# amp-33dbm.net
KiCad netlist of a schematic drawn in Altium Designer
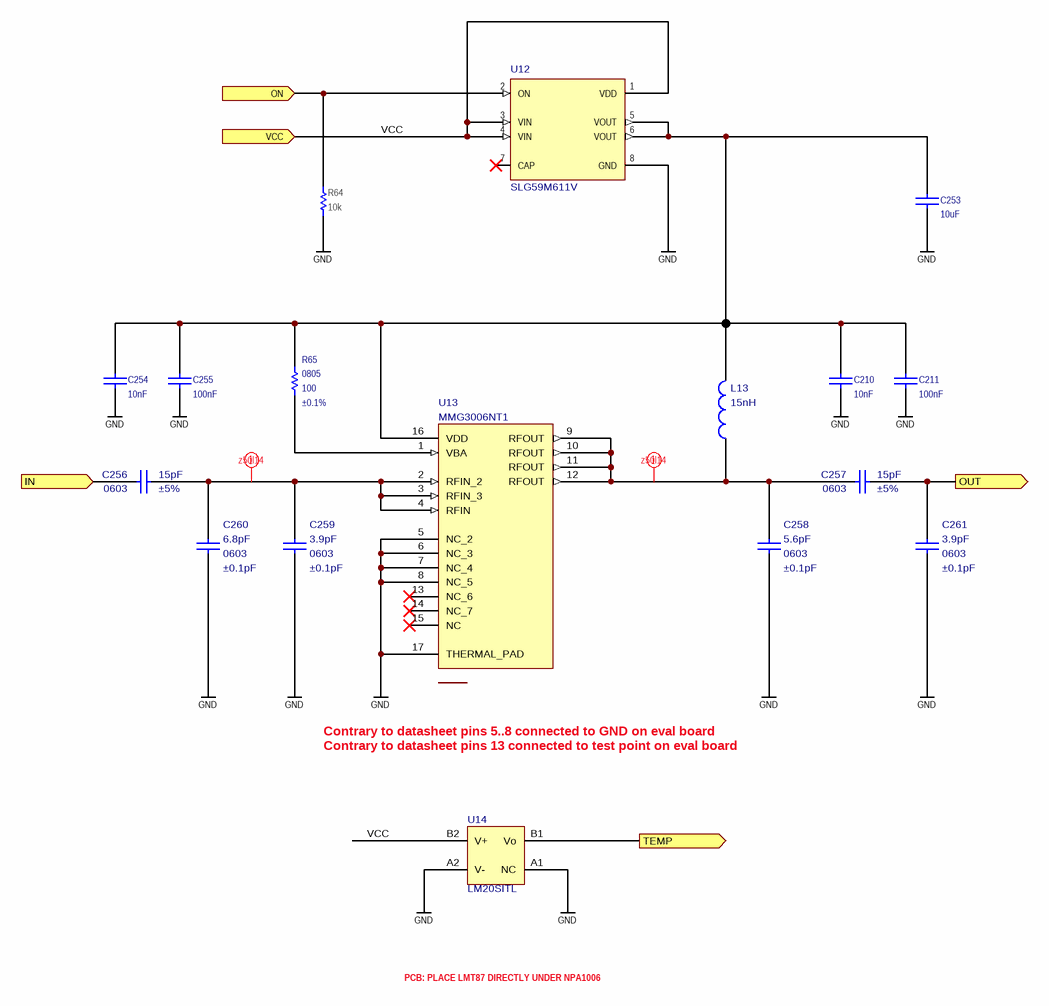
[diagram p0: amp-33dbm.SchDoc]

(export (version "E")
  (design (tool "Eeschema 10.0.6"))
  (components
    (comp (ref "C210")
      (value "10nF")
      (footprint "CAPC100X50X55L25N")
      (description "Ceramic Capacitor 10nF ±10% 50V X7R 0402")
      (fields (field (name "VOLTAGE") "50V") (field (name "MANUFACTURER") "Murata"))
      (libsource (lib "Graviton") (part "CAP 0402"))
    )
    (comp (ref "C211")
      (value "100nF")
      (footprint "CAPC100X50X55L25N")
      (description "Ceramic Capacitor 100nF ±10% 16V X7R 0402")
      (fields (field (name "VOLTAGE") "16V") (field (name "MANUFACTURER") "Murata"))
      (libsource (lib "Graviton") (part "CAP 0402"))
    )
    (comp (ref "C253")
      (value "10uF")
      (footprint "CAPC160X80X90L20N")
      (description "Ceramic Capacitor 10uF ±20% 25V X5R 0603")
      (fields (field (name "MANUFACTURER") "Murata") (field (name "VOLTAGE") "25V"))
      (libsource (lib "generic") (part "CAP 0603"))
    )
    (comp (ref "C254")
      (value "10nF")
      (footprint "CAPC100X50X55L25N")
      (description "Ceramic Capacitor 10nF ±10% 50V X7R 0402")
      (fields (field (name "VOLTAGE") "50V") (field (name "MANUFACTURER") "Murata"))
      (libsource (lib "Graviton") (part "CAP 0402"))
    )
    (comp (ref "C255")
      (value "100nF")
      (footprint "CAPC100X50X55L25N")
      (description "Ceramic Capacitor 100nF ±10% 16V X7R 0402")
      (fields (field (name "VOLTAGE") "16V") (field (name "MANUFACTURER") "Murata"))
      (libsource (lib "Graviton") (part "CAP 0402"))
    )
    (comp (ref "C256")
      (value "15pF")
      (footprint "CAPC160X80X90L20N")
      (description "Ceramic Capacitor 15pF ±5% NP0 0603")
      (fields
        (field (name "MANUFACTURER") "Murata")
        (field (name "TOLERANCE") "±5%")
        (field (name "VOLTAGE") "50V")
        (field (name "PACKAGE") "0603")
      )
      (libsource (lib "generic") (part "CAP"))
    )
    (comp (ref "C257")
      (value "15pF")
      (footprint "CAPC160X80X90L20N")
      (description "Ceramic Capacitor 15pF ±5% NP0 0603")
      (fields
        (field (name "MANUFACTURER") "Murata")
        (field (name "TOLERANCE") "±5%")
        (field (name "VOLTAGE") "50V")
        (field (name "PACKAGE") "0603")
      )
      (libsource (lib "generic") (part "CAP"))
    )
    (comp (ref "C258")
      (value "5.6pF")
      (footprint "CAPC160X80X90L20N")
      (description "Ceramic Capacitor 5.6pF ±0.1pF NP0 0603")
      (fields
        (field (name "MANUFACTURER") "AVX")
        (field (name "TOLERANCE") "±0.1pF")
        (field (name "VOLTAGE") "200V")
        (field (name "PACKAGE") "0603")
      )
      (libsource (lib "generic") (part "CAP"))
    )
    (comp (ref "C259")
      (value "3.9pF")
      (footprint "CAPC160X80X90L20N")
      (description "Ceramic Capacitor 3.9pF ±0.1pF NP0 0603")
      (fields
        (field (name "MANUFACTURER") "AVX")
        (field (name "TOLERANCE") "±0.1pF")
        (field (name "VOLTAGE") "200V")
        (field (name "PACKAGE") "0603")
      )
      (libsource (lib "generic") (part "CAP"))
    )
    (comp (ref "C260")
      (value "6.8pF")
      (footprint "CAPC160X80X90L20N")
      (description "Ceramic Capacitor 6.8pF ±0.1pF NP0 0603")
      (fields
        (field (name "MANUFACTURER") "AVX")
        (field (name "TOLERANCE") "±0.1pF")
        (field (name "VOLTAGE") "200V")
        (field (name "PACKAGE") "0603")
      )
      (libsource (lib "generic") (part "CAP"))
    )
    (comp (ref "C261")
      (value "3.9pF")
      (footprint "CAPC160X80X90L20N")
      (description "Ceramic Capacitor 3.9pF ±0.1pF NP0 0603")
      (fields
        (field (name "MANUFACTURER") "AVX")
        (field (name "TOLERANCE") "±0.1pF")
        (field (name "VOLTAGE") "200V")
        (field (name "PACKAGE") "0603")
      )
      (libsource (lib "generic") (part "CAP"))
    )
    (comp (ref "L13")
      (value "15nH")
      (footprint "1008CS")
      (description "Inductor 15nH 1A")
      (fields (field (name "MANUFACTURER") "Coilcraft") (field (name "Comment") "1008CS-150XJB"))
      (libsource (lib "generic") (part "INDUCTOR"))
    )
    (comp (ref "R64")
      (value "10k")
      (footprint "RESC1005X40N")
      (description "Thick Film Resistor 10k ±1% 0.1W 50V 0402")
      (fields (field (name "MANUFACTURER") "Panasonic") (field (name "TOLERANCE") "±1%"))
      (libsource (lib "generic") (part "RES"))
    )
    (comp (ref "R65")
      (value "100")
      (footprint "RESC2012X70N")
      (description "Thin Film Resistor 100 +/-0.1% SMD 0805")
      (fields
        (field (name "TOLERANCE") "±0.1%")
        (field (name "MANUFACTURER") "Susumu")
        (field (name "PACKAGE") "0805")
        (field (name "Comment") "RG2012P-101-B-T5")
      )
      (libsource (lib "generic") (part "RES"))
    )
    (comp (ref "U12")
      (value "SLG59M611V")
      (footprint "DFN200X150X80-8N")
      (description "High-Side Load Switch")
      (fields (field (name "MANUFACTURER") "Silego"))
      (libsource (lib "silego") (part "SLG59M611V"))
    )
    (comp (ref "U13")
      (value "MMG3006NT1")
      (footprint "nxp:QFN65P400X400X90-17N")
      (description "RF Amp Chip Single GP 2.4GHz 6V 16-Pin QFN EP T/R")
      (fields (field (name "MANUFACTURER") "NXP Semiconductors"))
      (libsource (lib "nxp") (part "MMG3006NT1"))
    )
    (comp (ref "U14")
      (value "LM20SITL")
      (footprint "YZR-4")
      (description "Analog Temperature Sensor")
      (fields (field (name "MANUFACTURER") "Texas Instruments"))
      (libsource (lib "ti") (part "LM20SITL"))
    )
  )
  (nets
    (net (code "1") (name "/IN") (class "Default")
      (node (ref "C256") (pin "1") (pinfunction "1_1") (pintype "passive"))
    )
    (net (code "2") (name "/ON") (class "Default")
      (node (ref "R64") (pin "2") (pinfunction "2_2") (pintype "passive"))
      (node (ref "U12") (pin "2") (pinfunction "ON_2") (pintype "input"))
    )
    (net (code "3") (name "/OUT") (class "Default")
      (node (ref "C257") (pin "2") (pinfunction "2_2") (pintype "passive"))
      (node (ref "C261") (pin "2") (pinfunction "2_2") (pintype "passive"))
    )
    (net (code "4") (name "/TEMP") (class "Default")
      (node (ref "U14") (pin "B1") (pinfunction "Vo_B1") (pintype "passive"))
    )
    (net (code "5") (name "/VCC") (class "Default")
      (node (ref "U12") (pin "1") (pinfunction "VDD_1") (pintype "power_in"))
      (node (ref "U12") (pin "3") (pinfunction "VIN_3") (pintype "input"))
      (node (ref "U12") (pin "4") (pinfunction "VIN_4") (pintype "input"))
      (node (ref "U14") (pin "B2") (pinfunction "V+_B2") (pintype "passive"))
    )
    (net (code "6") (name "GND") (class "Default")
      (node (ref "C210") (pin "1") (pinfunction "1_1") (pintype "passive"))
      (node (ref "C211") (pin "1") (pinfunction "1_1") (pintype "passive"))
      (node (ref "C253") (pin "1") (pinfunction "1_1") (pintype "passive"))
      (node (ref "C254") (pin "1") (pinfunction "1_1") (pintype "passive"))
      (node (ref "C255") (pin "1") (pinfunction "1_1") (pintype "passive"))
      (node (ref "C258") (pin "1") (pinfunction "1_1") (pintype "passive"))
      (node (ref "C259") (pin "1") (pinfunction "1_1") (pintype "passive"))
      (node (ref "C260") (pin "1") (pinfunction "1_1") (pintype "passive"))
      (node (ref "C261") (pin "1") (pinfunction "1_1") (pintype "passive"))
      (node (ref "R64") (pin "1") (pinfunction "1_1") (pintype "passive"))
      (node (ref "U12") (pin "8") (pinfunction "GND_8") (pintype "power_in"))
      (node (ref "U13") (pin "17") (pinfunction "THERMAL_PAD_17") (pintype "passive"))
      (node (ref "U13") (pin "5") (pinfunction "NC_2_5") (pintype "passive"))
      (node (ref "U13") (pin "6") (pinfunction "NC_3_6") (pintype "passive"))
      (node (ref "U13") (pin "7") (pinfunction "NC_4_7") (pintype "passive"))
      (node (ref "U13") (pin "8") (pinfunction "NC_5_8") (pintype "passive"))
      (node (ref "U14") (pin "A1") (pinfunction "NC_A1") (pintype "passive"))
      (node (ref "U14") (pin "A2") (pinfunction "V-_A2") (pintype "passive"))
    )
    (net (code "7") (name "Net-(C257-Pad1)") (class "Default")
      (node (ref "C257") (pin "1") (pinfunction "1_1") (pintype "passive"))
      (node (ref "C258") (pin "2") (pinfunction "2_2") (pintype "passive"))
      (node (ref "L13") (pin "1") (pinfunction "1_1") (pintype "passive"))
      (node (ref "U13") (pin "10") (pinfunction "RFOUT_10") (pintype "output"))
      (node (ref "U13") (pin "11") (pinfunction "RFOUT_11") (pintype "output"))
      (node (ref "U13") (pin "12") (pinfunction "RFOUT_12") (pintype "output"))
      (node (ref "U13") (pin "9") (pinfunction "RFOUT_9") (pintype "output"))
    )
    (net (code "8") (name "Net-(U13-RFIN)") (class "Default")
      (node (ref "C256") (pin "2") (pinfunction "2_2") (pintype "passive"))
      (node (ref "C259") (pin "2") (pinfunction "2_2") (pintype "passive"))
      (node (ref "C260") (pin "2") (pinfunction "2_2") (pintype "passive"))
      (node (ref "U13") (pin "2") (pinfunction "RFIN_2_2") (pintype "input"))
      (node (ref "U13") (pin "3") (pinfunction "RFIN_3_3") (pintype "input"))
      (node (ref "U13") (pin "4") (pinfunction "RFIN_4") (pintype "input"))
    )
    (net (code "9") (name "Net-(U13-VBA)") (class "Default")
      (node (ref "R65") (pin "1") (pinfunction "1_1") (pintype "passive"))
      (node (ref "U13") (pin "1") (pinfunction "VBA_1") (pintype "input"))
    )
    (net (code "10") (name "Net-(U13-VDD)") (class "Default")
      (node (ref "C210") (pin "2") (pinfunction "2_2") (pintype "passive"))
      (node (ref "C211") (pin "2") (pinfunction "2_2") (pintype "passive"))
      (node (ref "C253") (pin "2") (pinfunction "2_2") (pintype "passive"))
      (node (ref "C254") (pin "2") (pinfunction "2_2") (pintype "passive"))
      (node (ref "C255") (pin "2") (pinfunction "2_2") (pintype "passive"))
      (node (ref "L13") (pin "2") (pinfunction "2_2") (pintype "passive"))
      (node (ref "R65") (pin "2") (pinfunction "2_2") (pintype "passive"))
      (node (ref "U12") (pin "5") (pinfunction "VOUT_5") (pintype "output"))
      (node (ref "U12") (pin "6") (pinfunction "VOUT_6") (pintype "output"))
      (node (ref "U13") (pin "16") (pinfunction "VDD_16") (pintype "power_in"))
    )
    (net (code "11") (name "unconnected-(U12-CAP-Pad7)") (class "Default")
      (node (ref "U12") (pin "7") (pinfunction "CAP_7") (pintype "passive+no_connect"))
    )
    (net (code "12") (name "unconnected-(U13-NC-Pad15)") (class "Default")
      (node (ref "U13") (pin "15") (pinfunction "NC_15") (pintype "passive+no_connect"))
    )
    (net (code "13") (name "unconnected-(U13-NC_6-Pad13)") (class "Default")
      (node (ref "U13") (pin "13") (pinfunction "NC_6_13") (pintype "passive+no_connect"))
    )
    (net (code "14") (name "unconnected-(U13-NC_7-Pad14)") (class "Default")
      (node (ref "U13") (pin "14") (pinfunction "NC_7_14") (pintype "passive+no_connect"))
    )
  )
)
